# Connectors.net
KiCad netlist of a schematic drawn in Altium Designer
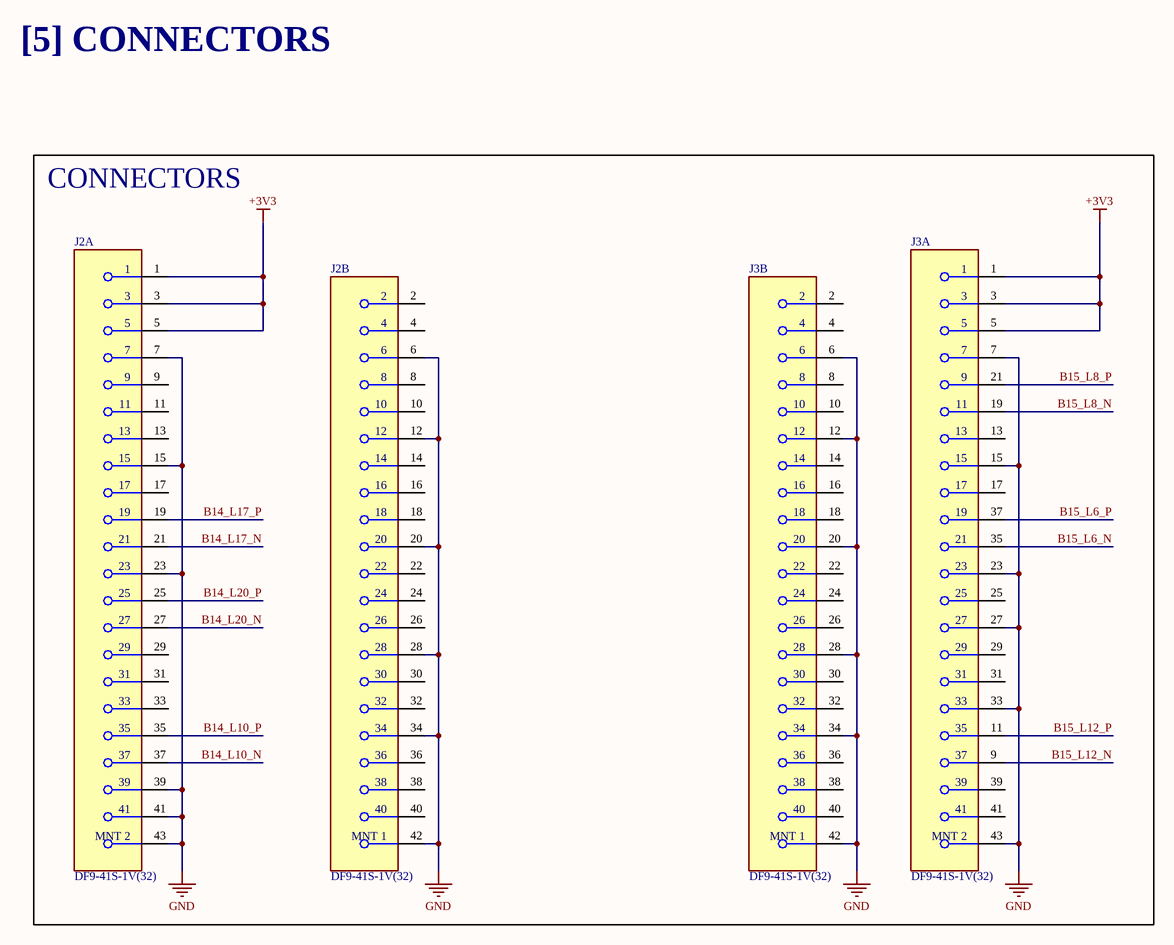
[diagram p0: Connectors.SchDoc]

(export (version "E")
  (design (tool "Eeschema 10.0.6"))
  (components
    (comp (ref "J2")
      (value "DF9-41S-1V(32)")
      (footprint "FP-DF9-41S-1V_32-MFG")
      (description "CONN RCPT 41POS SMD TIN")
      (libsource (lib "Altium Content Vault") (part "bccd7f0a3439813622a0e048c062efe"))
    )
    (comp (ref "J3")
      (value "DF9-41S-1V(32)")
      (footprint "FP-DF9-41S-1V_32-MFG")
      (description "CONN RCPT 41POS SMD TIN")
      (libsource (lib "Altium Content Vault") (part "bccd7f0a3439813622a0e048c062efe"))
    )
  )
  (nets
    (net (code "1") (name "+3V3") (class "Default")
      (node (ref "J2") (pin "1") (pinfunction "1_1") (pintype "passive"))
      (node (ref "J2") (pin "3") (pinfunction "3_3") (pintype "passive"))
      (node (ref "J2") (pin "5") (pinfunction "5_5") (pintype "passive"))
      (node (ref "J3") (pin "1") (pinfunction "1_1") (pintype "passive"))
      (node (ref "J3") (pin "3") (pinfunction "3_3") (pintype "passive"))
      (node (ref "J3") (pin "5") (pinfunction "5_5") (pintype "passive"))
    )
    (net (code "2") (name "/B14_L10_N") (class "Default")
      (node (ref "J2") (pin "37") (pinfunction "37_37") (pintype "passive"))
    )
    (net (code "3") (name "/B14_L10_P") (class "Default")
      (node (ref "J2") (pin "35") (pinfunction "35_35") (pintype "passive"))
    )
    (net (code "4") (name "/B14_L17_N") (class "Default")
      (node (ref "J2") (pin "21") (pinfunction "21_21") (pintype "passive"))
    )
    (net (code "5") (name "/B14_L17_P") (class "Default")
      (node (ref "J2") (pin "19") (pinfunction "19_19") (pintype "passive"))
    )
    (net (code "6") (name "/B14_L20_N") (class "Default")
      (node (ref "J2") (pin "27") (pinfunction "27_27") (pintype "passive"))
    )
    (net (code "7") (name "/B14_L20_P") (class "Default")
      (node (ref "J2") (pin "25") (pinfunction "25_25") (pintype "passive"))
    )
    (net (code "8") (name "/B15_L6_N") (class "Default")
      (node (ref "J3") (pin "35") (pinfunction "35_35") (pintype "passive"))
    )
    (net (code "9") (name "/B15_L6_P") (class "Default")
      (node (ref "J3") (pin "37") (pinfunction "37_37") (pintype "passive"))
    )
    (net (code "10") (name "/B15_L8_N") (class "Default")
      (node (ref "J3") (pin "19") (pinfunction "19_19") (pintype "passive"))
    )
    (net (code "11") (name "/B15_L8_P") (class "Default")
      (node (ref "J3") (pin "21") (pinfunction "21_21") (pintype "passive"))
    )
    (net (code "12") (name "/B15_L12_N") (class "Default")
      (node (ref "J3") (pin "9") (pinfunction "9_9") (pintype "passive"))
    )
    (net (code "13") (name "/B15_L12_P") (class "Default")
      (node (ref "J3") (pin "11") (pinfunction "11_11") (pintype "passive"))
    )
    (net (code "14") (name "GND") (class "Default")
      (node (ref "J2") (pin "12") (pinfunction "12_12") (pintype "passive"))
      (node (ref "J2") (pin "15") (pinfunction "15_15") (pintype "passive"))
      (node (ref "J2") (pin "20") (pinfunction "20_20") (pintype "passive"))
      (node (ref "J2") (pin "23") (pinfunction "23_23") (pintype "passive"))
      (node (ref "J2") (pin "28") (pinfunction "28_28") (pintype "passive"))
      (node (ref "J2") (pin "34") (pinfunction "34_34") (pintype "passive"))
      (node (ref "J2") (pin "39") (pinfunction "39_39") (pintype "passive"))
      (node (ref "J2") (pin "41") (pinfunction "41_41") (pintype "passive"))
      (node (ref "J2") (pin "42") (pinfunction "MNT_1_42") (pintype "passive"))
      (node (ref "J2") (pin "43") (pinfunction "MNT_2_43") (pintype "passive"))
      (node (ref "J2") (pin "6") (pinfunction "6_6") (pintype "passive"))
      (node (ref "J2") (pin "7") (pinfunction "7_7") (pintype "passive"))
      (node (ref "J3") (pin "12") (pinfunction "12_12") (pintype "passive"))
      (node (ref "J3") (pin "15") (pinfunction "15_15") (pintype "passive"))
      (node (ref "J3") (pin "20") (pinfunction "20_20") (pintype "passive"))
      (node (ref "J3") (pin "23") (pinfunction "23_23") (pintype "passive"))
      (node (ref "J3") (pin "27") (pinfunction "27_27") (pintype "passive"))
      (node (ref "J3") (pin "28") (pinfunction "28_28") (pintype "passive"))
      (node (ref "J3") (pin "33") (pinfunction "33_33") (pintype "passive"))
      (node (ref "J3") (pin "34") (pinfunction "34_34") (pintype "passive"))
      (node (ref "J3") (pin "42") (pinfunction "MNT_1_42") (pintype "passive"))
      (node (ref "J3") (pin "43") (pinfunction "MNT_2_43") (pintype "passive"))
      (node (ref "J3") (pin "6") (pinfunction "6_6") (pintype "passive"))
      (node (ref "J3") (pin "7") (pinfunction "7_7") (pintype "passive"))
    )
    (net (code "15") (name "unconnected-(J2-Pad2)") (class "Default")
      (node (ref "J2") (pin "2") (pinfunction "2_2") (pintype "passive"))
    )
    (net (code "16") (name "unconnected-(J2-Pad4)") (class "Default")
      (node (ref "J2") (pin "4") (pinfunction "4_4") (pintype "passive"))
    )
    (net (code "17") (name "unconnected-(J2-Pad8)") (class "Default")
      (node (ref "J2") (pin "8") (pinfunction "8_8") (pintype "passive"))
    )
    (net (code "18") (name "unconnected-(J2-Pad9)") (class "Default")
      (node (ref "J2") (pin "9") (pinfunction "9_9") (pintype "passive"))
    )
    (net (code "19") (name "unconnected-(J2-Pad10)") (class "Default")
      (node (ref "J2") (pin "10") (pinfunction "10_10") (pintype "passive"))
    )
    (net (code "20") (name "unconnected-(J2-Pad11)") (class "Default")
      (node (ref "J2") (pin "11") (pinfunction "11_11") (pintype "passive"))
    )
    (net (code "21") (name "unconnected-(J2-Pad13)") (class "Default")
      (node (ref "J2") (pin "13") (pinfunction "13_13") (pintype "passive"))
    )
    (net (code "22") (name "unconnected-(J2-Pad14)") (class "Default")
      (node (ref "J2") (pin "14") (pinfunction "14_14") (pintype "passive"))
    )
    (net (code "23") (name "unconnected-(J2-Pad16)") (class "Default")
      (node (ref "J2") (pin "16") (pinfunction "16_16") (pintype "passive"))
    )
    (net (code "24") (name "unconnected-(J2-Pad17)") (class "Default")
      (node (ref "J2") (pin "17") (pinfunction "17_17") (pintype "passive"))
    )
    (net (code "25") (name "unconnected-(J2-Pad18)") (class "Default")
      (node (ref "J2") (pin "18") (pinfunction "18_18") (pintype "passive"))
    )
    (net (code "26") (name "unconnected-(J2-Pad22)") (class "Default")
      (node (ref "J2") (pin "22") (pinfunction "22_22") (pintype "passive"))
    )
    (net (code "27") (name "unconnected-(J2-Pad24)") (class "Default")
      (node (ref "J2") (pin "24") (pinfunction "24_24") (pintype "passive"))
    )
    (net (code "28") (name "unconnected-(J2-Pad26)") (class "Default")
      (node (ref "J2") (pin "26") (pinfunction "26_26") (pintype "passive"))
    )
    (net (code "29") (name "unconnected-(J2-Pad29)") (class "Default")
      (node (ref "J2") (pin "29") (pinfunction "29_29") (pintype "passive"))
    )
    (net (code "30") (name "unconnected-(J2-Pad30)") (class "Default")
      (node (ref "J2") (pin "30") (pinfunction "30_30") (pintype "passive"))
    )
    (net (code "31") (name "unconnected-(J2-Pad31)") (class "Default")
      (node (ref "J2") (pin "31") (pinfunction "31_31") (pintype "passive"))
    )
    (net (code "32") (name "unconnected-(J2-Pad32)") (class "Default")
      (node (ref "J2") (pin "32") (pinfunction "32_32") (pintype "passive"))
    )
    (net (code "33") (name "unconnected-(J2-Pad33)") (class "Default")
      (node (ref "J2") (pin "33") (pinfunction "33_33") (pintype "passive"))
    )
    (net (code "34") (name "unconnected-(J2-Pad36)") (class "Default")
      (node (ref "J2") (pin "36") (pinfunction "36_36") (pintype "passive"))
    )
    (net (code "35") (name "unconnected-(J2-Pad38)") (class "Default")
      (node (ref "J2") (pin "38") (pinfunction "38_38") (pintype "passive"))
    )
    (net (code "36") (name "unconnected-(J2-Pad40)") (class "Default")
      (node (ref "J2") (pin "40") (pinfunction "40_40") (pintype "passive"))
    )
    (net (code "37") (name "unconnected-(J3-Pad2)") (class "Default")
      (node (ref "J3") (pin "2") (pinfunction "2_2") (pintype "passive"))
    )
    (net (code "38") (name "unconnected-(J3-Pad4)") (class "Default")
      (node (ref "J3") (pin "4") (pinfunction "4_4") (pintype "passive"))
    )
    (net (code "39") (name "unconnected-(J3-Pad8)") (class "Default")
      (node (ref "J3") (pin "8") (pinfunction "8_8") (pintype "passive"))
    )
    (net (code "40") (name "unconnected-(J3-Pad10)") (class "Default")
      (node (ref "J3") (pin "10") (pinfunction "10_10") (pintype "passive"))
    )
    (net (code "41") (name "unconnected-(J3-Pad13)") (class "Default")
      (node (ref "J3") (pin "13") (pinfunction "13_13") (pintype "passive"))
    )
    (net (code "42") (name "unconnected-(J3-Pad14)") (class "Default")
      (node (ref "J3") (pin "14") (pinfunction "14_14") (pintype "passive"))
    )
    (net (code "43") (name "unconnected-(J3-Pad16)") (class "Default")
      (node (ref "J3") (pin "16") (pinfunction "16_16") (pintype "passive"))
    )
    (net (code "44") (name "unconnected-(J3-Pad17)") (class "Default")
      (node (ref "J3") (pin "17") (pinfunction "17_17") (pintype "passive"))
    )
    (net (code "45") (name "unconnected-(J3-Pad18)") (class "Default")
      (node (ref "J3") (pin "18") (pinfunction "18_18") (pintype "passive"))
    )
    (net (code "46") (name "unconnected-(J3-Pad22)") (class "Default")
      (node (ref "J3") (pin "22") (pinfunction "22_22") (pintype "passive"))
    )
    (net (code "47") (name "unconnected-(J3-Pad24)") (class "Default")
      (node (ref "J3") (pin "24") (pinfunction "24_24") (pintype "passive"))
    )
    (net (code "48") (name "unconnected-(J3-Pad25)") (class "Default")
      (node (ref "J3") (pin "25") (pinfunction "25_25") (pintype "passive"))
    )
    (net (code "49") (name "unconnected-(J3-Pad26)") (class "Default")
      (node (ref "J3") (pin "26") (pinfunction "26_26") (pintype "passive"))
    )
    (net (code "50") (name "unconnected-(J3-Pad29)") (class "Default")
      (node (ref "J3") (pin "29") (pinfunction "29_29") (pintype "passive"))
    )
    (net (code "51") (name "unconnected-(J3-Pad30)") (class "Default")
      (node (ref "J3") (pin "30") (pinfunction "30_30") (pintype "passive"))
    )
    (net (code "52") (name "unconnected-(J3-Pad31)") (class "Default")
      (node (ref "J3") (pin "31") (pinfunction "31_31") (pintype "passive"))
    )
    (net (code "53") (name "unconnected-(J3-Pad32)") (class "Default")
      (node (ref "J3") (pin "32") (pinfunction "32_32") (pintype "passive"))
    )
    (net (code "54") (name "unconnected-(J3-Pad36)") (class "Default")
      (node (ref "J3") (pin "36") (pinfunction "36_36") (pintype "passive"))
    )
    (net (code "55") (name "unconnected-(J3-Pad38)") (class "Default")
      (node (ref "J3") (pin "38") (pinfunction "38_38") (pintype "passive"))
    )
    (net (code "56") (name "unconnected-(J3-Pad39)") (class "Default")
      (node (ref "J3") (pin "39") (pinfunction "39_39") (pintype "passive"))
    )
    (net (code "57") (name "unconnected-(J3-Pad40)") (class "Default")
      (node (ref "J3") (pin "40") (pinfunction "40_40") (pintype "passive"))
    )
    (net (code "58") (name "unconnected-(J3-Pad41)") (class "Default")
      (node (ref "J3") (pin "41") (pinfunction "41_41") (pintype "passive"))
    )
  )
)
